# v8_4_controler.net
KiCad netlist of a schematic drawn in EAGLE
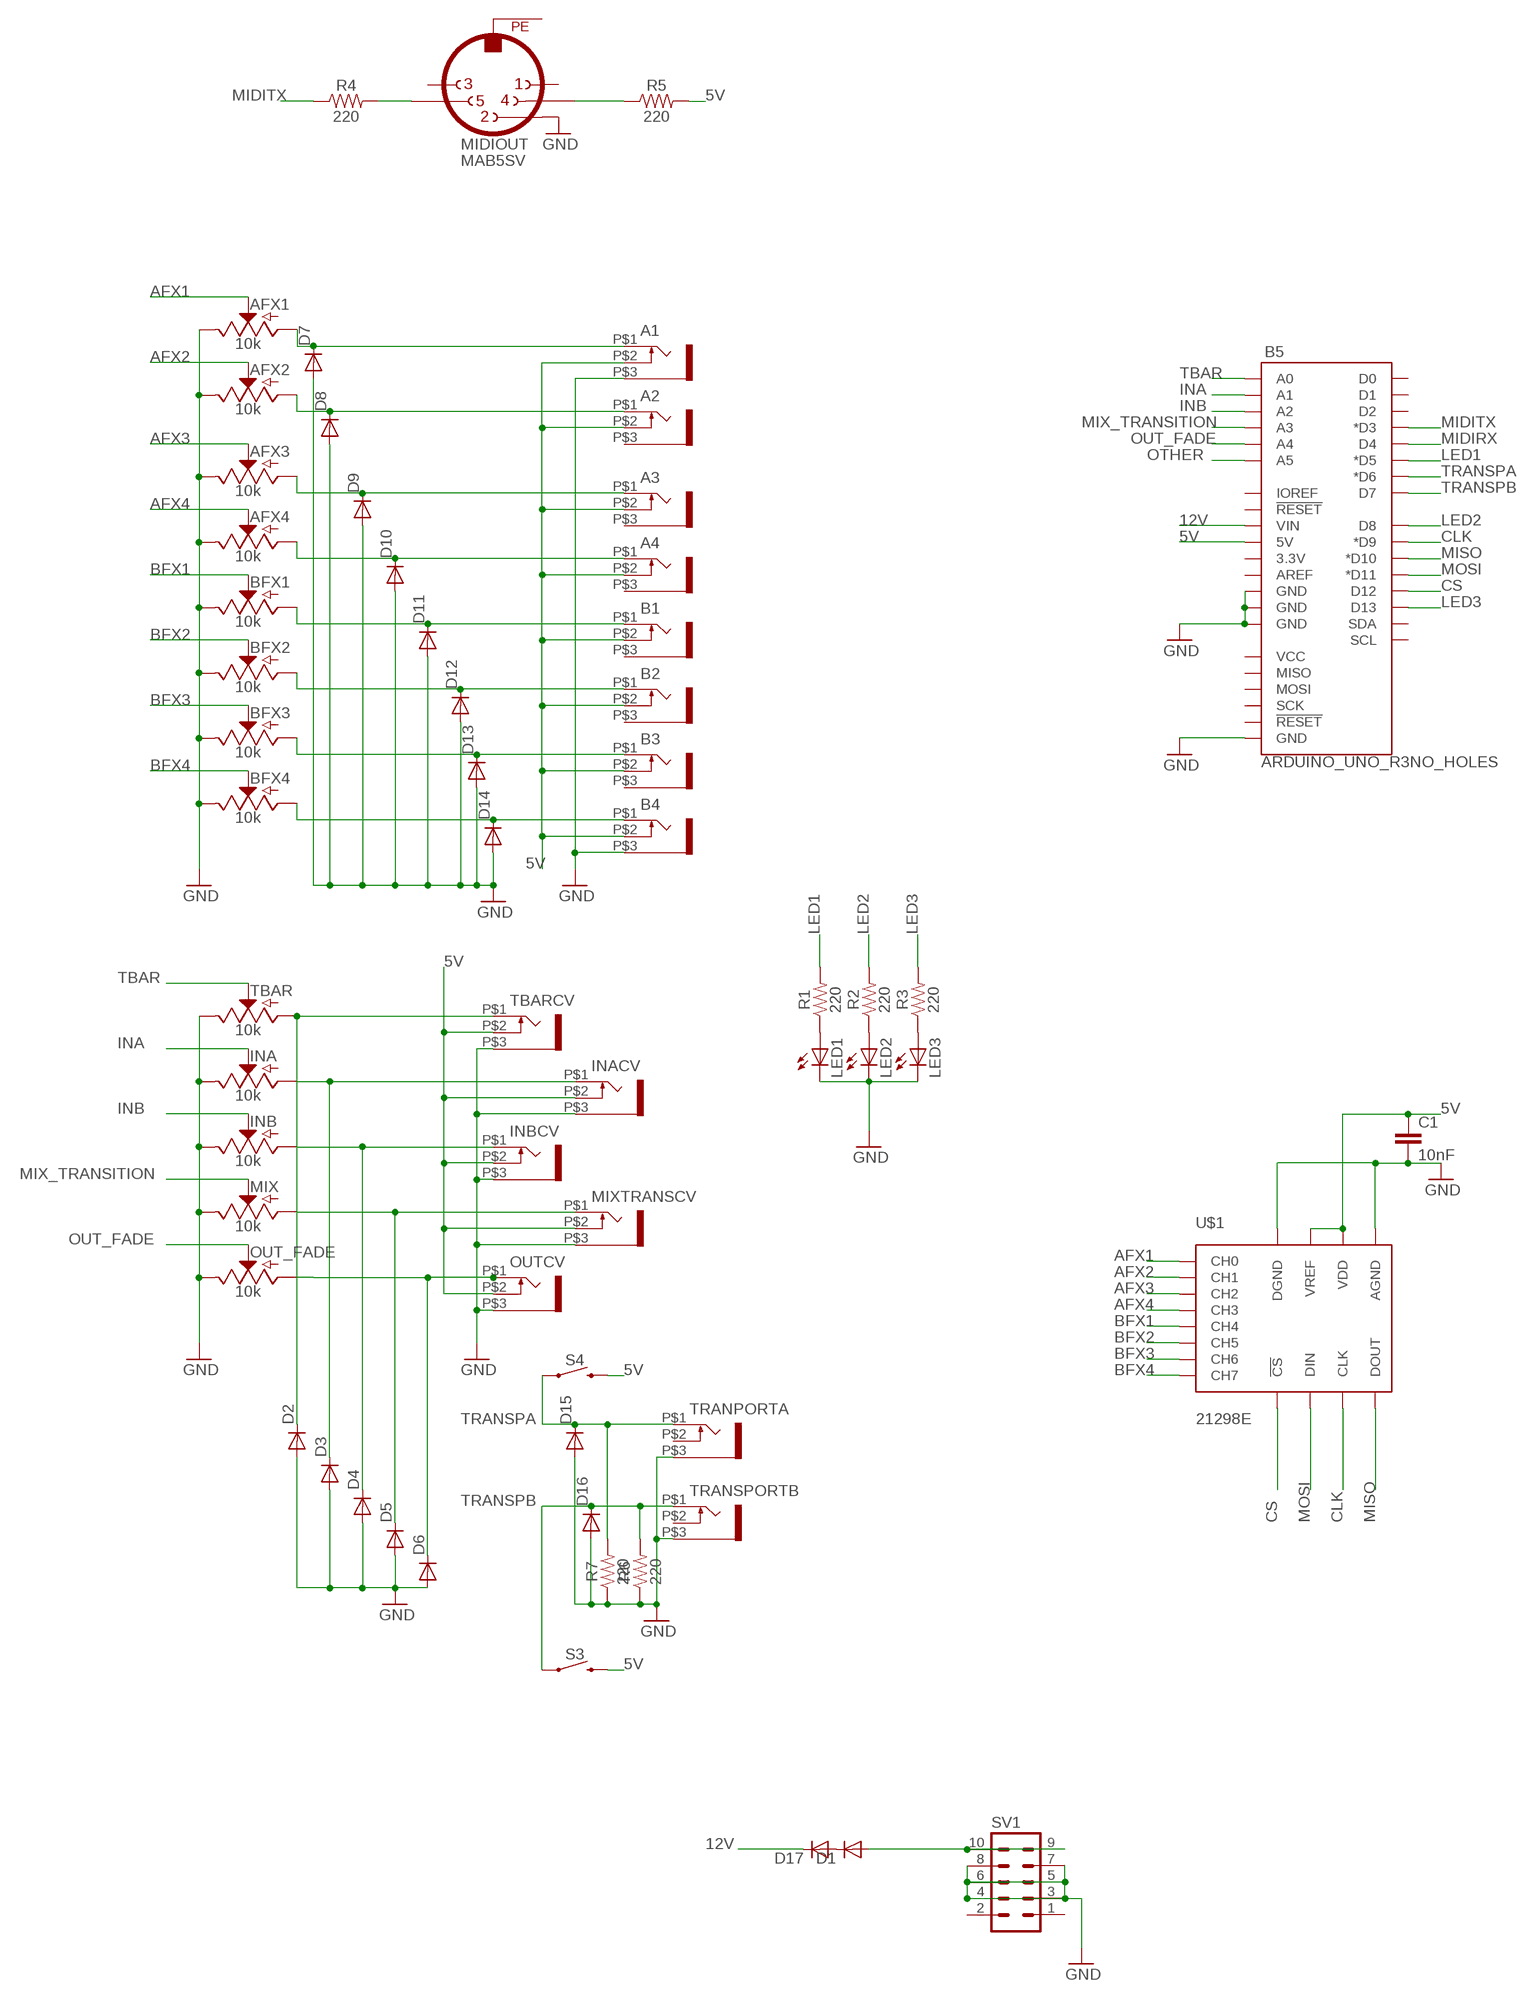
[diagram p0: schematic, sheet 1]

(export (version "E")
  (design (tool "Eeschema 10.0.6"))
  (components
    (comp (ref "A1")
      (value "WQP-PJ301M-12_JACK")
      (footprint "eagle-import:WQP-PJ301M-12_JACK")
      (fields (field (name "SPICEPREFIX") "U"))
      (libsource (lib "eagle-import") (part "WQP-PJ301M-12_JACK"))
    )
    (comp (ref "A2")
      (value "WQP-PJ301M-12_JACK")
      (footprint "eagle-import:WQP-PJ301M-12_JACK")
      (fields (field (name "SPICEPREFIX") "U"))
      (libsource (lib "eagle-import") (part "WQP-PJ301M-12_JACK"))
    )
    (comp (ref "A3")
      (value "WQP-PJ301M-12_JACK")
      (footprint "eagle-import:WQP-PJ301M-12_JACK")
      (fields (field (name "SPICEPREFIX") "U"))
      (libsource (lib "eagle-import") (part "WQP-PJ301M-12_JACK"))
    )
    (comp (ref "A4")
      (value "WQP-PJ301M-12_JACK")
      (footprint "eagle-import:WQP-PJ301M-12_JACK")
      (fields (field (name "SPICEPREFIX") "U"))
      (libsource (lib "eagle-import") (part "WQP-PJ301M-12_JACK"))
    )
    (comp (ref "AFX1")
      (value "10k")
      (footprint "eagle-import:POT-PTH-ALPS")
      (libsource (lib "eagle-import") (part "POTENTIOMETER-PTH-9MM-1/20W-20%"))
    )
    (comp (ref "AFX2")
      (value "10k")
      (footprint "eagle-import:POT-PTH-ALPS")
      (libsource (lib "eagle-import") (part "POTENTIOMETER-PTH-9MM-1/20W-20%"))
    )
    (comp (ref "AFX3")
      (value "10k")
      (footprint "eagle-import:POT-PTH-ALPS")
      (libsource (lib "eagle-import") (part "POTENTIOMETER-PTH-9MM-1/20W-20%"))
    )
    (comp (ref "AFX4")
      (value "10k")
      (footprint "eagle-import:POT-PTH-ALPS")
      (libsource (lib "eagle-import") (part "POTENTIOMETER-PTH-9MM-1/20W-20%"))
    )
    (comp (ref "B1")
      (value "WQP-PJ301M-12_JACK")
      (footprint "eagle-import:WQP-PJ301M-12_JACK")
      (fields (field (name "SPICEPREFIX") "U"))
      (libsource (lib "eagle-import") (part "WQP-PJ301M-12_JACK"))
    )
    (comp (ref "B2")
      (value "WQP-PJ301M-12_JACK")
      (footprint "eagle-import:WQP-PJ301M-12_JACK")
      (fields (field (name "SPICEPREFIX") "U"))
      (libsource (lib "eagle-import") (part "WQP-PJ301M-12_JACK"))
    )
    (comp (ref "B3")
      (value "WQP-PJ301M-12_JACK")
      (footprint "eagle-import:WQP-PJ301M-12_JACK")
      (fields (field (name "SPICEPREFIX") "U"))
      (libsource (lib "eagle-import") (part "WQP-PJ301M-12_JACK"))
    )
    (comp (ref "B4")
      (value "WQP-PJ301M-12_JACK")
      (footprint "eagle-import:WQP-PJ301M-12_JACK")
      (fields (field (name "SPICEPREFIX") "U"))
      (libsource (lib "eagle-import") (part "WQP-PJ301M-12_JACK"))
    )
    (comp (ref "B5")
      (value "ARDUINO_UNO_R3NO_HOLES")
      (footprint "eagle-import:ARDUINO_R3_NO_HOLES")
      (libsource (lib "eagle-import") (part "ARDUINO_UNO_R3NO_HOLES"))
    )
    (comp (ref "BFX1")
      (value "10k")
      (footprint "eagle-import:POT-PTH-ALPS")
      (libsource (lib "eagle-import") (part "POTENTIOMETER-PTH-9MM-1/20W-20%"))
    )
    (comp (ref "BFX2")
      (value "10k")
      (footprint "eagle-import:POT-PTH-ALPS")
      (libsource (lib "eagle-import") (part "POTENTIOMETER-PTH-9MM-1/20W-20%"))
    )
    (comp (ref "BFX3")
      (value "10k")
      (footprint "eagle-import:POT-PTH-ALPS")
      (libsource (lib "eagle-import") (part "POTENTIOMETER-PTH-9MM-1/20W-20%"))
    )
    (comp (ref "BFX4")
      (value "10k")
      (footprint "eagle-import:POT-PTH-ALPS")
      (libsource (lib "eagle-import") (part "POTENTIOMETER-PTH-9MM-1/20W-20%"))
    )
    (comp (ref "C1")
      (value "10nF")
      (footprint "eagle-import:CAP-PTH-10MM")
      (libsource (lib "eagle-import") (part "10NF-PTH-10MM-10000V-1-%"))
    )
    (comp (ref "D1")
      (value "1N4004")
      (footprint "eagle-import:DO41-10")
      (libsource (lib "eagle-import") (part "1N4004"))
    )
    (comp (ref "D2")
      (value "1N4004")
      (footprint "eagle-import:DO41-10")
      (libsource (lib "eagle-import") (part "1N4004"))
    )
    (comp (ref "D3")
      (value "1N4004")
      (footprint "eagle-import:DO41-10")
      (libsource (lib "eagle-import") (part "1N4004"))
    )
    (comp (ref "D4")
      (value "1N4004")
      (footprint "eagle-import:DO41-10")
      (libsource (lib "eagle-import") (part "1N4004"))
    )
    (comp (ref "D5")
      (value "1N4004")
      (footprint "eagle-import:DO41-10")
      (libsource (lib "eagle-import") (part "1N4004"))
    )
    (comp (ref "D6")
      (value "1N4004")
      (footprint "eagle-import:DO41-10")
      (libsource (lib "eagle-import") (part "1N4004"))
    )
    (comp (ref "D7")
      (value "1N4004")
      (footprint "eagle-import:DO41-10")
      (libsource (lib "eagle-import") (part "1N4004"))
    )
    (comp (ref "D8")
      (value "1N4004")
      (footprint "eagle-import:DO41-10")
      (libsource (lib "eagle-import") (part "1N4004"))
    )
    (comp (ref "D9")
      (value "1N4004")
      (footprint "eagle-import:DO41-10")
      (libsource (lib "eagle-import") (part "1N4004"))
    )
    (comp (ref "D10")
      (value "1N4004")
      (footprint "eagle-import:DO41-10")
      (libsource (lib "eagle-import") (part "1N4004"))
    )
    (comp (ref "D11")
      (value "1N4004")
      (footprint "eagle-import:DO41-10")
      (libsource (lib "eagle-import") (part "1N4004"))
    )
    (comp (ref "D12")
      (value "1N4004")
      (footprint "eagle-import:DO41-10")
      (libsource (lib "eagle-import") (part "1N4004"))
    )
    (comp (ref "D13")
      (value "1N4004")
      (footprint "eagle-import:DO41-10")
      (libsource (lib "eagle-import") (part "1N4004"))
    )
    (comp (ref "D14")
      (value "1N4004")
      (footprint "eagle-import:DO41-10")
      (libsource (lib "eagle-import") (part "1N4004"))
    )
    (comp (ref "D15")
      (value "1N4004")
      (footprint "eagle-import:DO41-10")
      (libsource (lib "eagle-import") (part "1N4004"))
    )
    (comp (ref "D16")
      (value "1N4004")
      (footprint "eagle-import:DO41-10")
      (libsource (lib "eagle-import") (part "1N4004"))
    )
    (comp (ref "D17")
      (value "1N4004")
      (footprint "eagle-import:DO41-10")
      (libsource (lib "eagle-import") (part "1N4004"))
    )
    (comp (ref "INA")
      (value "10k")
      (footprint "eagle-import:POT-PTH-ALPS")
      (libsource (lib "eagle-import") (part "POTENTIOMETER-PTH-9MM-1/20W-20%"))
    )
    (comp (ref "INACV")
      (value "WQP-PJ301M-12_JACK")
      (footprint "eagle-import:WQP-PJ301M-12_JACK")
      (fields (field (name "SPICEPREFIX") "U"))
      (libsource (lib "eagle-import") (part "WQP-PJ301M-12_JACK"))
    )
    (comp (ref "INB")
      (value "10k")
      (footprint "eagle-import:POT-PTH-ALPS")
      (libsource (lib "eagle-import") (part "POTENTIOMETER-PTH-9MM-1/20W-20%"))
    )
    (comp (ref "INBCV")
      (value "WQP-PJ301M-12_JACK")
      (footprint "eagle-import:WQP-PJ301M-12_JACK")
      (fields (field (name "SPICEPREFIX") "U"))
      (libsource (lib "eagle-import") (part "WQP-PJ301M-12_JACK"))
    )
    (comp (ref "LED1")
      (value "LED3MM")
      (footprint "eagle-import:LED3MM")
      (libsource (lib "eagle-import") (part "LED3MM"))
    )
    (comp (ref "LED2")
      (value "LED3MM")
      (footprint "eagle-import:LED3MM")
      (libsource (lib "eagle-import") (part "LED3MM"))
    )
    (comp (ref "LED3")
      (value "LED3MM")
      (footprint "eagle-import:LED3MM")
      (libsource (lib "eagle-import") (part "LED3MM"))
    )
    (comp (ref "MIDIOUT")
      (value "MAB5SV")
      (footprint "eagle-import:MAB5SV")
      (libsource (lib "eagle-import") (part "MAB5SV"))
    )
    (comp (ref "MIX")
      (value "10k")
      (footprint "eagle-import:POT-PTH-ALPS")
      (libsource (lib "eagle-import") (part "POTENTIOMETER-PTH-9MM-1/20W-20%"))
    )
    (comp (ref "MIXTRANSCV")
      (value "WQP-PJ301M-12_JACK")
      (footprint "eagle-import:WQP-PJ301M-12_JACK")
      (fields (field (name "SPICEPREFIX") "U"))
      (libsource (lib "eagle-import") (part "WQP-PJ301M-12_JACK"))
    )
    (comp (ref "OUTCV")
      (value "WQP-PJ301M-12_JACK")
      (footprint "eagle-import:WQP-PJ301M-12_JACK")
      (fields (field (name "SPICEPREFIX") "U"))
      (libsource (lib "eagle-import") (part "WQP-PJ301M-12_JACK"))
    )
    (comp (ref "OUT_FADE")
      (value "10k")
      (footprint "eagle-import:POT-PTH-ALPS")
      (libsource (lib "eagle-import") (part "POTENTIOMETER-PTH-9MM-1/20W-20%"))
    )
    (comp (ref "R1")
      (value "220")
      (footprint "eagle-import:AXIAL-0.3")
      (libsource (lib "eagle-import") (part "10MOHM-HORIZ-1/4W-5%"))
    )
    (comp (ref "R2")
      (value "220")
      (footprint "eagle-import:AXIAL-0.3")
      (libsource (lib "eagle-import") (part "10MOHM-HORIZ-1/4W-5%"))
    )
    (comp (ref "R3")
      (value "220")
      (footprint "eagle-import:AXIAL-0.3")
      (libsource (lib "eagle-import") (part "10MOHM-HORIZ-1/4W-5%"))
    )
    (comp (ref "R4")
      (value "220")
      (footprint "eagle-import:AXIAL-0.3")
      (libsource (lib "eagle-import") (part "10MOHM-HORIZ-1/4W-5%"))
    )
    (comp (ref "R5")
      (value "220")
      (footprint "eagle-import:AXIAL-0.3")
      (libsource (lib "eagle-import") (part "10MOHM-HORIZ-1/4W-5%"))
    )
    (comp (ref "R6")
      (value "220")
      (footprint "eagle-import:AXIAL-0.3")
      (libsource (lib "eagle-import") (part "10MOHM-HORIZ-1/4W-5%"))
    )
    (comp (ref "R7")
      (value "220")
      (footprint "eagle-import:AXIAL-0.3")
      (libsource (lib "eagle-import") (part "10MOHM-HORIZ-1/4W-5%"))
    )
    (comp (ref "S3")
      (value "MOMENTARY-SWITCH-SPST-PTH-6.0MM")
      (footprint "eagle-import:TACTILE_SWITCH_PTH_6.0MM")
      (libsource (lib "eagle-import") (part "MOMENTARY-SWITCH-SPST-PTH-6.0MM"))
    )
    (comp (ref "S4")
      (value "MOMENTARY-SWITCH-SPST-PTH-6.0MM")
      (footprint "eagle-import:TACTILE_SWITCH_PTH_6.0MM")
      (libsource (lib "eagle-import") (part "MOMENTARY-SWITCH-SPST-PTH-6.0MM"))
    )
    (comp (ref "SV1")
      (value "MA05-2")
      (footprint "eagle-import:MA05-2")
      (libsource (lib "eagle-import") (part "MA05-2"))
    )
    (comp (ref "TBAR")
      (value "10k")
      (footprint "eagle-import:POT-PTH-ALPS")
      (libsource (lib "eagle-import") (part "POTENTIOMETER-PTH-9MM-1/20W-20%"))
    )
    (comp (ref "TBARCV")
      (value "WQP-PJ301M-12_JACK")
      (footprint "eagle-import:WQP-PJ301M-12_JACK")
      (fields (field (name "SPICEPREFIX") "U"))
      (libsource (lib "eagle-import") (part "WQP-PJ301M-12_JACK"))
    )
    (comp (ref "TRANPORTA")
      (value "WQP-PJ301M-12_JACK")
      (footprint "eagle-import:WQP-PJ301M-12_JACK")
      (fields (field (name "SPICEPREFIX") "U"))
      (libsource (lib "eagle-import") (part "WQP-PJ301M-12_JACK"))
    )
    (comp (ref "TRANSPORTB")
      (value "WQP-PJ301M-12_JACK")
      (footprint "eagle-import:WQP-PJ301M-12_JACK")
      (fields (field (name "SPICEPREFIX") "U"))
      (libsource (lib "eagle-import") (part "WQP-PJ301M-12_JACK"))
    )
    (comp (ref "U$1")
      (value "21298E")
      (footprint "eagle-import:PDIP16")
      (libsource (lib "eagle-import") (part "21298E"))
    )
  )
  (nets
    (net (code "1") (name "/5V") (class "Default")
      (node (ref "A1") (pin "P$2") (pinfunction "3_P$2") (pintype "passive"))
      (node (ref "A2") (pin "P$2") (pinfunction "3_P$2") (pintype "passive"))
      (node (ref "A3") (pin "P$2") (pinfunction "3_P$2") (pintype "passive"))
      (node (ref "A4") (pin "P$2") (pinfunction "3_P$2") (pintype "passive"))
      (node (ref "B1") (pin "P$2") (pinfunction "3_P$2") (pintype "passive"))
      (node (ref "B2") (pin "P$2") (pinfunction "3_P$2") (pintype "passive"))
      (node (ref "B3") (pin "P$2") (pinfunction "3_P$2") (pintype "passive"))
      (node (ref "B4") (pin "P$2") (pinfunction "3_P$2") (pintype "passive"))
      (node (ref "B5") (pin "5V") (pinfunction "5V_5V") (pintype "bidirectional"))
      (node (ref "C1") (pin "1") (pinfunction "1_1") (pintype "passive"))
      (node (ref "INACV") (pin "P$2") (pinfunction "3_P$2") (pintype "passive"))
      (node (ref "INBCV") (pin "P$2") (pinfunction "3_P$2") (pintype "passive"))
      (node (ref "MIXTRANSCV") (pin "P$2") (pinfunction "3_P$2") (pintype "passive"))
      (node (ref "OUTCV") (pin "P$2") (pinfunction "3_P$2") (pintype "passive"))
      (node (ref "R5") (pin "P$2") (pinfunction "2_P$2") (pintype "passive"))
      (node (ref "S3") (pin "3") (pinfunction "2_3") (pintype "passive"))
      (node (ref "S4") (pin "3") (pinfunction "2_3") (pintype "passive"))
      (node (ref "TBARCV") (pin "P$2") (pinfunction "3_P$2") (pintype "passive"))
      (node (ref "U$1") (pin "P$15") (pinfunction "VREF_P$15") (pintype "bidirectional"))
      (node (ref "U$1") (pin "P$16") (pinfunction "VDD_P$16") (pintype "bidirectional"))
    )
    (net (code "2") (name "/12V") (class "Default")
      (node (ref "B5") (pin "VIN") (pinfunction "VIN_VIN") (pintype "bidirectional"))
      (node (ref "D17") (pin "C") (pinfunction "C_C") (pintype "passive"))
    )
    (net (code "3") (name "/AFX1") (class "Default")
      (node (ref "AFX1") (pin "P$2") (pinfunction "S_P$2") (pintype "passive"))
      (node (ref "U$1") (pin "P$1") (pinfunction "CH0_P$1") (pintype "bidirectional"))
    )
    (net (code "4") (name "/AFX2") (class "Default")
      (node (ref "AFX2") (pin "P$2") (pinfunction "S_P$2") (pintype "passive"))
      (node (ref "U$1") (pin "P$2") (pinfunction "CH1_P$2") (pintype "bidirectional"))
    )
    (net (code "5") (name "/AFX3") (class "Default")
      (node (ref "AFX3") (pin "P$2") (pinfunction "S_P$2") (pintype "passive"))
      (node (ref "U$1") (pin "P$3") (pinfunction "CH2_P$3") (pintype "bidirectional"))
    )
    (net (code "6") (name "/AFX4") (class "Default")
      (node (ref "AFX4") (pin "P$2") (pinfunction "S_P$2") (pintype "passive"))
      (node (ref "U$1") (pin "P$4") (pinfunction "CH3_P$4") (pintype "bidirectional"))
    )
    (net (code "7") (name "/BFX1") (class "Default")
      (node (ref "BFX1") (pin "P$2") (pinfunction "S_P$2") (pintype "passive"))
      (node (ref "U$1") (pin "P$5") (pinfunction "CH4_P$5") (pintype "bidirectional"))
    )
    (net (code "8") (name "/BFX2") (class "Default")
      (node (ref "BFX2") (pin "P$2") (pinfunction "S_P$2") (pintype "passive"))
      (node (ref "U$1") (pin "P$6") (pinfunction "CH5_P$6") (pintype "bidirectional"))
    )
    (net (code "9") (name "/BFX3") (class "Default")
      (node (ref "BFX3") (pin "P$2") (pinfunction "S_P$2") (pintype "passive"))
      (node (ref "U$1") (pin "P$7") (pinfunction "CH6_P$7") (pintype "bidirectional"))
    )
    (net (code "10") (name "/BFX4") (class "Default")
      (node (ref "BFX4") (pin "P$2") (pinfunction "S_P$2") (pintype "passive"))
      (node (ref "U$1") (pin "P$8") (pinfunction "CH7_P$8") (pintype "bidirectional"))
    )
    (net (code "11") (name "/CLK") (class "Default")
      (node (ref "B5") (pin "D9") (pinfunction "*D9_D9") (pintype "bidirectional"))
      (node (ref "U$1") (pin "P$13") (pinfunction "CLK_P$13") (pintype "bidirectional"))
    )
    (net (code "12") (name "/CS") (class "Default")
      (node (ref "B5") (pin "D12") (pinfunction "D12_D12") (pintype "bidirectional"))
      (node (ref "U$1") (pin "P$10") (pinfunction "~{CS}_P$10") (pintype "bidirectional"))
    )
    (net (code "13") (name "/INA") (class "Default")
      (node (ref "B5") (pin "A1") (pinfunction "A1_A1") (pintype "bidirectional"))
      (node (ref "INA") (pin "P$2") (pinfunction "S_P$2") (pintype "passive"))
    )
    (net (code "14") (name "/INB") (class "Default")
      (node (ref "B5") (pin "A2") (pinfunction "A2_A2") (pintype "bidirectional"))
      (node (ref "INB") (pin "P$2") (pinfunction "S_P$2") (pintype "passive"))
    )
    (net (code "15") (name "/LED1") (class "Default")
      (node (ref "B5") (pin "D5") (pinfunction "*D5_D5") (pintype "bidirectional"))
      (node (ref "R1") (pin "P$2") (pinfunction "2_P$2") (pintype "passive"))
    )
    (net (code "16") (name "/LED2") (class "Default")
      (node (ref "B5") (pin "D8") (pinfunction "D8_D8") (pintype "bidirectional"))
      (node (ref "R2") (pin "P$2") (pinfunction "2_P$2") (pintype "passive"))
    )
    (net (code "17") (name "/LED3") (class "Default")
      (node (ref "B5") (pin "D13") (pinfunction "D13_D13") (pintype "bidirectional"))
      (node (ref "R3") (pin "P$2") (pinfunction "2_P$2") (pintype "passive"))
    )
    (net (code "18") (name "/MIDIRX") (class "Default")
      (node (ref "B5") (pin "D4") (pinfunction "D4_D4") (pintype "bidirectional"))
    )
    (net (code "19") (name "/MIDITX") (class "Default")
      (node (ref "B5") (pin "D3") (pinfunction "*D3_D3") (pintype "bidirectional"))
      (node (ref "R4") (pin "P$1") (pinfunction "1_P$1") (pintype "passive"))
    )
    (net (code "20") (name "/MISO") (class "Default")
      (node (ref "B5") (pin "D10") (pinfunction "*D10_D10") (pintype "bidirectional"))
      (node (ref "U$1") (pin "P$12") (pinfunction "DOUT_P$12") (pintype "bidirectional"))
    )
    (net (code "21") (name "/MIX_TRANSITION") (class "Default")
      (node (ref "B5") (pin "A3") (pinfunction "A3_A3") (pintype "bidirectional"))
      (node (ref "MIX") (pin "P$2") (pinfunction "S_P$2") (pintype "passive"))
    )
    (net (code "22") (name "/MOSI") (class "Default")
      (node (ref "B5") (pin "D11") (pinfunction "*D11_D11") (pintype "bidirectional"))
      (node (ref "U$1") (pin "P$11") (pinfunction "DIN_P$11") (pintype "bidirectional"))
    )
    (net (code "23") (name "/OTHER") (class "Default")
      (node (ref "B5") (pin "A5") (pinfunction "A5_A5") (pintype "bidirectional"))
    )
    (net (code "24") (name "/OUT_FADE") (class "Default")
      (node (ref "B5") (pin "A4") (pinfunction "A4_A4") (pintype "bidirectional"))
      (node (ref "OUT_FADE") (pin "P$2") (pinfunction "S_P$2") (pintype "passive"))
    )
    (net (code "25") (name "/PE") (class "Default")
      (node (ref "MIDIOUT") (pin "PE") (pinfunction "PE_PE") (pintype "power_in"))
    )
    (net (code "26") (name "/TBAR") (class "Default")
      (node (ref "B5") (pin "A0") (pinfunction "A0_A0") (pintype "bidirectional"))
      (node (ref "TBAR") (pin "P$2") (pinfunction "S_P$2") (pintype "passive"))
    )
    (net (code "27") (name "/TRANSPA") (class "Default")
      (node (ref "B5") (pin "D6") (pinfunction "*D6_D6") (pintype "bidirectional"))
      (node (ref "D15") (pin "C") (pinfunction "C_C") (pintype "passive"))
      (node (ref "R7") (pin "P$2") (pinfunction "2_P$2") (pintype "passive"))
      (node (ref "S4") (pin "1") (pinfunction "1_1") (pintype "passive"))
      (node (ref "TRANPORTA") (pin "P$1") (pinfunction "2_P$1") (pintype "passive"))
    )
    (net (code "28") (name "/TRANSPB") (class "Default")
      (node (ref "B5") (pin "D7") (pinfunction "D7_D7") (pintype "bidirectional"))
      (node (ref "D16") (pin "C") (pinfunction "C_C") (pintype "passive"))
      (node (ref "R6") (pin "P$2") (pinfunction "2_P$2") (pintype "passive"))
      (node (ref "S3") (pin "1") (pinfunction "1_1") (pintype "passive"))
      (node (ref "TRANSPORTB") (pin "P$1") (pinfunction "2_P$1") (pintype "passive"))
    )
    (net (code "29") (name "GND") (class "Default")
      (node (ref "A1") (pin "P$3") (pinfunction "1_P$3") (pintype "passive"))
      (node (ref "AFX1") (pin "P$1") (pinfunction "E_P$1") (pintype "passive"))
      (node (ref "AFX2") (pin "P$1") (pinfunction "E_P$1") (pintype "passive"))
      (node (ref "AFX3") (pin "P$1") (pinfunction "E_P$1") (pintype "passive"))
      (node (ref "AFX4") (pin "P$1") (pinfunction "E_P$1") (pintype "passive"))
      (node (ref "B4") (pin "P$3") (pinfunction "1_P$3") (pintype "passive"))
      (node (ref "B5") (pin "GND@1") (pinfunction "GND_GND@1") (pintype "bidirectional"))
      (node (ref "B5") (pin "GND@2") (pinfunction "GND_GND@2") (pintype "bidirectional"))
      (node (ref "B5") (pin "GND@3") (pinfunction "GND_GND@3") (pintype "bidirectional"))
      (node (ref "B5") (pin "GND@4") (pinfunction "GND_GND@4") (pintype "bidirectional"))
      (node (ref "BFX1") (pin "P$1") (pinfunction "E_P$1") (pintype "passive"))
      (node (ref "BFX2") (pin "P$1") (pinfunction "E_P$1") (pintype "passive"))
      (node (ref "BFX3") (pin "P$1") (pinfunction "E_P$1") (pintype "passive"))
      (node (ref "BFX4") (pin "P$1") (pinfunction "E_P$1") (pintype "passive"))
      (node (ref "C1") (pin "2") (pinfunction "2_2") (pintype "passive"))
      (node (ref "D10") (pin "A") (pinfunction "A_A") (pintype "passive"))
      (node (ref "D11") (pin "A") (pinfunction "A_A") (pintype "passive"))
      (node (ref "D12") (pin "A") (pinfunction "A_A") (pintype "passive"))
      (node (ref "D13") (pin "A") (pinfunction "A_A") (pintype "passive"))
      (node (ref "D14") (pin "A") (pinfunction "A_A") (pintype "passive"))
      (node (ref "D15") (pin "A") (pinfunction "A_A") (pintype "passive"))
      (node (ref "D16") (pin "A") (pinfunction "A_A") (pintype "passive"))
      (node (ref "D2") (pin "A") (pinfunction "A_A") (pintype "passive"))
      (node (ref "D3") (pin "A") (pinfunction "A_A") (pintype "passive"))
      (node (ref "D4") (pin "A") (pinfunction "A_A") (pintype "passive"))
      (node (ref "D5") (pin "A") (pinfunction "A_A") (pintype "passive"))
      (node (ref "D6") (pin "A") (pinfunction "A_A") (pintype "passive"))
      (node (ref "D7") (pin "A") (pinfunction "A_A") (pintype "passive"))
      (node (ref "D8") (pin "A") (pinfunction "A_A") (pintype "passive"))
      (node (ref "D9") (pin "A") (pinfunction "A_A") (pintype "passive"))
      (node (ref "INA") (pin "P$1") (pinfunction "E_P$1") (pintype "passive"))
      (node (ref "INACV") (pin "P$3") (pinfunction "1_P$3") (pintype "passive"))
      (node (ref "INB") (pin "P$1") (pinfunction "E_P$1") (pintype "passive"))
      (node (ref "INBCV") (pin "P$3") (pinfunction "1_P$3") (pintype "passive"))
      (node (ref "LED1") (pin "K") (pinfunction "C_K") (pintype "passive"))
      (node (ref "LED2") (pin "K") (pinfunction "C_K") (pintype "passive"))
      (node (ref "LED3") (pin "K") (pinfunction "C_K") (pintype "passive"))
      (node (ref "MIDIOUT") (pin "2") (pinfunction "2_2") (pintype "passive"))
      (node (ref "MIX") (pin "P$1") (pinfunction "E_P$1") (pintype "passive"))
      (node (ref "MIXTRANSCV") (pin "P$3") (pinfunction "1_P$3") (pintype "passive"))
      (node (ref "OUTCV") (pin "P$3") (pinfunction "1_P$3") (pintype "passive"))
      (node (ref "OUT_FADE") (pin "P$1") (pinfunction "E_P$1") (pintype "passive"))
      (node (ref "R6") (pin "P$1") (pinfunction "1_P$1") (pintype "passive"))
      (node (ref "R7") (pin "P$1") (pinfunction "1_P$1") (pintype "passive"))
      (node (ref "SV1") (pin "3") (pinfunction "3_3") (pintype "passive"))
      (node (ref "SV1") (pin "4") (pinfunction "4_4") (pintype "passive"))
      (node (ref "SV1") (pin "5") (pinfunction "5_5") (pintype "passive"))
      (node (ref "SV1") (pin "6") (pinfunction "6_6") (pintype "passive"))
      (node (ref "SV1") (pin "7") (pinfunction "7_7") (pintype "passive"))
      (node (ref "SV1") (pin "8") (pinfunction "8_8") (pintype "passive"))
      (node (ref "TBAR") (pin "P$1") (pinfunction "E_P$1") (pintype "passive"))
      (node (ref "TBARCV") (pin "P$3") (pinfunction "1_P$3") (pintype "passive"))
      (node (ref "TRANPORTA") (pin "P$3") (pinfunction "1_P$3") (pintype "passive"))
      (node (ref "TRANSPORTB") (pin "P$3") (pinfunction "1_P$3") (pintype "passive"))
      (node (ref "U$1") (pin "P$14") (pinfunction "AGND_P$14") (pintype "bidirectional"))
      (node (ref "U$1") (pin "P$9") (pinfunction "DGND_P$9") (pintype "bidirectional"))
    )
    (net (code "30") (name "Net-(A1-2)") (class "Default")
      (node (ref "A1") (pin "P$1") (pinfunction "2_P$1") (pintype "passive"))
      (node (ref "AFX1") (pin "P$3") (pinfunction "A_P$3") (pintype "passive"))
      (node (ref "D7") (pin "C") (pinfunction "C_C") (pintype "passive"))
    )
    (net (code "31") (name "Net-(A2-2)") (class "Default")
      (node (ref "A2") (pin "P$1") (pinfunction "2_P$1") (pintype "passive"))
      (node (ref "AFX2") (pin "P$3") (pinfunction "A_P$3") (pintype "passive"))
      (node (ref "D8") (pin "C") (pinfunction "C_C") (pintype "passive"))
    )
    (net (code "32") (name "Net-(A3-2)") (class "Default")
      (node (ref "A3") (pin "P$1") (pinfunction "2_P$1") (pintype "passive"))
      (node (ref "AFX3") (pin "P$3") (pinfunction "A_P$3") (pintype "passive"))
      (node (ref "D9") (pin "C") (pinfunction "C_C") (pintype "passive"))
    )
    (net (code "33") (name "Net-(A4-2)") (class "Default")
      (node (ref "A4") (pin "P$1") (pinfunction "2_P$1") (pintype "passive"))
      (node (ref "AFX4") (pin "P$3") (pinfunction "A_P$3") (pintype "passive"))
      (node (ref "D10") (pin "C") (pinfunction "C_C") (pintype "passive"))
    )
    (net (code "34") (name "Net-(B1-2)") (class "Default")
      (node (ref "B1") (pin "P$1") (pinfunction "2_P$1") (pintype "passive"))
      (node (ref "BFX1") (pin "P$3") (pinfunction "A_P$3") (pintype "passive"))
      (node (ref "D11") (pin "C") (pinfunction "C_C") (pintype "passive"))
    )
    (net (code "35") (name "Net-(B2-2)") (class "Default")
      (node (ref "B2") (pin "P$1") (pinfunction "2_P$1") (pintype "passive"))
      (node (ref "BFX2") (pin "P$3") (pinfunction "A_P$3") (pintype "passive"))
      (node (ref "D12") (pin "C") (pinfunction "C_C") (pintype "passive"))
    )
    (net (code "36") (name "Net-(B3-2)") (class "Default")
      (node (ref "B3") (pin "P$1") (pinfunction "2_P$1") (pintype "passive"))
      (node (ref "BFX3") (pin "P$3") (pinfunction "A_P$3") (pintype "passive"))
      (node (ref "D13") (pin "C") (pinfunction "C_C") (pintype "passive"))
    )
    (net (code "37") (name "Net-(B4-2)") (class "Default")
      (node (ref "B4") (pin "P$1") (pinfunction "2_P$1") (pintype "passive"))
      (node (ref "BFX4") (pin "P$3") (pinfunction "A_P$3") (pintype "passive"))
      (node (ref "D14") (pin "C") (pinfunction "C_C") (pintype "passive"))
    )
    (net (code "38") (name "Net-(D1-PadA)") (class "Default")
      (node (ref "D1") (pin "A") (pinfunction "A_A") (pintype "passive"))
      (node (ref "SV1") (pin "10") (pinfunction "10_10") (pintype "passive"))
      (node (ref "SV1") (pin "9") (pinfunction "9_9") (pintype "passive"))
    )
    (net (code "39") (name "Net-(D1-PadC)") (class "Default")
      (node (ref "D1") (pin "C") (pinfunction "C_C") (pintype "passive"))
      (node (ref "D17") (pin "A") (pinfunction "A_A") (pintype "passive"))
    )
    (net (code "40") (name "Net-(INA-A)") (class "Default")
      (node (ref "D3") (pin "C") (pinfunction "C_C") (pintype "passive"))
      (node (ref "INA") (pin "P$3") (pinfunction "A_P$3") (pintype "passive"))
      (node (ref "INACV") (pin "P$1") (pinfunction "2_P$1") (pintype "passive"))
    )
    (net (code "41") (name "Net-(INB-A)") (class "Default")
      (node (ref "D4") (pin "C") (pinfunction "C_C") (pintype "passive"))
      (node (ref "INB") (pin "P$3") (pinfunction "A_P$3") (pintype "passive"))
      (node (ref "INBCV") (pin "P$1") (pinfunction "2_P$1") (pintype "passive"))
    )
    (net (code "42") (name "Net-(MIX-A)") (class "Default")
      (node (ref "D5") (pin "C") (pinfunction "C_C") (pintype "passive"))
      (node (ref "MIX") (pin "P$3") (pinfunction "A_P$3") (pintype "passive"))
      (node (ref "MIXTRANSCV") (pin "P$1") (pinfunction "2_P$1") (pintype "passive"))
    )
    (net (code "43") (name "Net-(OUTCV-2)") (class "Default")
      (node (ref "D6") (pin "C") (pinfunction "C_C") (pintype "passive"))
      (node (ref "OUTCV") (pin "P$1") (pinfunction "2_P$1") (pintype "passive"))
      (node (ref "OUT_FADE") (pin "P$3") (pinfunction "A_P$3") (pintype "passive"))
    )
    (net (code "44") (name "Net-(R1-1)") (class "Default")
      (node (ref "LED1") (pin "A") (pinfunction "A_A") (pintype "passive"))
      (node (ref "R1") (pin "P$1") (pinfunction "1_P$1") (pintype "passive"))
    )
    (net (code "45") (name "Net-(R2-1)") (class "Default")
      (node (ref "LED2") (pin "A") (pinfunction "A_A") (pintype "passive"))
      (node (ref "R2") (pin "P$1") (pinfunction "1_P$1") (pintype "passive"))
    )
    (net (code "46") (name "Net-(R3-1)") (class "Default")
      (node (ref "LED3") (pin "A") (pinfunction "A_A") (pintype "passive"))
      (node (ref "R3") (pin "P$1") (pinfunction "1_P$1") (pintype "passive"))
    )
    (net (code "47") (name "Net-(R4-2)") (class "Default")
      (node (ref "MIDIOUT") (pin "5") (pinfunction "5_5") (pintype "passive"))
      (node (ref "R4") (pin "P$2") (pinfunction "2_P$2") (pintype "passive"))
    )
    (net (code "48") (name "Net-(R5-1)") (class "Default")
      (node (ref "MIDIOUT") (pin "4") (pinfunction "4_4") (pintype "passive"))
      (node (ref "R5") (pin "P$1") (pinfunction "1_P$1") (pintype "passive"))
    )
    (net (code "49") (name "Net-(TBAR-A)") (class "Default")
      (node (ref "D2") (pin "C") (pinfunction "C_C") (pintype "passive"))
      (node (ref "TBAR") (pin "P$3") (pinfunction "A_P$3") (pintype "passive"))
      (node (ref "TBARCV") (pin "P$1") (pinfunction "2_P$1") (pintype "passive"))
    )
    (net (code "50") (name "unconnected-(A2-1-PadP$3)") (class "Default")
      (node (ref "A2") (pin "P$3") (pinfunction "1_P$3") (pintype "passive"))
    )
    (net (code "51") (name "unconnected-(A3-1-PadP$3)") (class "Default")
      (node (ref "A3") (pin "P$3") (pinfunction "1_P$3") (pintype "passive"))
    )
    (net (code "52") (name "unconnected-(A4-1-PadP$3)") (class "Default")
      (node (ref "A4") (pin "P$3") (pinfunction "1_P$3") (pintype "passive"))
    )
    (net (code "53") (name "unconnected-(B1-1-PadP$3)") (class "Default")
      (node (ref "B1") (pin "P$3") (pinfunction "1_P$3") (pintype "passive"))
    )
    (net (code "54") (name "unconnected-(B2-1-PadP$3)") (class "Default")
      (node (ref "B2") (pin "P$3") (pinfunction "1_P$3") (pintype "passive"))
    )
    (net (code "55") (name "unconnected-(B3-1-PadP$3)") (class "Default")
      (node (ref "B3") (pin "P$3") (pinfunction "1_P$3") (pintype "passive"))
    )
    (net (code "56") (name "unconnected-(B5-Pad3.3V)") (class "Default")
      (node (ref "B5") (pin "3.3V") (pinfunction "3.3V_3.3V") (pintype "bidirectional"))
    )
    (net (code "57") (name "unconnected-(B5-PadAREF)") (class "Default")
      (node (ref "B5") (pin "AREF") (pinfunction "AREF_AREF") (pintype "bidirectional"))
    )
    (net (code "58") (name "unconnected-(B5-PadD0)") (class "Default")
      (node (ref "B5") (pin "D0") (pinfunction "D0_D0") (pintype "bidirectional"))
    )
    (net (code "59") (name "unconnected-(B5-PadD1)") (class "Default")
      (node (ref "B5") (pin "D1") (pinfunction "D1_D1") (pintype "bidirectional"))
    )
    (net (code "60") (name "unconnected-(B5-PadD2)") (class "Default")
      (node (ref "B5") (pin "D2") (pinfunction "D2_D2") (pintype "bidirectional"))
    )
    (net (code "61") (name "unconnected-(B5-PadIOREF)") (class "Default")
      (node (ref "B5") (pin "IOREF") (pinfunction "IOREF_IOREF") (pintype "bidirectional"))
    )
    (net (code "62") (name "unconnected-(B5-PadMISO)") (class "Default")
      (node (ref "B5") (pin "MISO") (pinfunction "MISO_MISO") (pintype "bidirectional"))
    )
    (net (code "63") (name "unconnected-(B5-PadMOSI)") (class "Default")
      (node (ref "B5") (pin "MOSI") (pinfunction "MOSI_MOSI") (pintype "bidirectional"))
    )
    (net (code "64") (name "unconnected-(B5-PadSCK)") (class "Default")
      (node (ref "B5") (pin "SCK") (pinfunction "SCK_SCK") (pintype "bidirectional"))
    )
    (net (code "65") (name "unconnected-(B5-PadSCL)") (class "Default")
      (node (ref "B5") (pin "SCL") (pinfunction "SCL_SCL") (pintype "bidirectional"))
    )
    (net (code "66") (name "unconnected-(B5-PadSDA)") (class "Default")
      (node (ref "B5") (pin "SDA") (pinfunction "SDA_SDA") (pintype "bidirectional"))
    )
    (net (code "67") (name "unconnected-(B5-PadVCC)") (class "Default")
      (node (ref "B5") (pin "VCC") (pinfunction "VCC_VCC") (pintype "bidirectional"))
    )
    (net (code "68") (name "unconnected-(B5-~{RESET}-PadRESET@1)") (class "Default")
      (node (ref "B5") (pin "RESET@1") (pinfunction "~{RESET}_RESET@1") (pintype "bidirectional"))
    )
    (net (code "69") (name "unconnected-(B5-~{RESET}-PadRESET@2)") (class "Default")
      (node (ref "B5") (pin "RESET@2") (pinfunction "~{RESET}_RESET@2") (pintype "bidirectional"))
    )
    (net (code "70") (name "unconnected-(MIDIOUT-Pad1)") (class "Default")
      (node (ref "MIDIOUT") (pin "1") (pinfunction "1_1") (pintype "passive"))
    )
    (net (code "71") (name "unconnected-(MIDIOUT-Pad3)") (class "Default")
      (node (ref "MIDIOUT") (pin "3") (pinfunction "3_3") (pintype "passive"))
    )
    (net (code "72") (name "unconnected-(SV1-Pad1)") (class "Default")
      (node (ref "SV1") (pin "1") (pinfunction "1_1") (pintype "passive"))
    )
    (net (code "73") (name "unconnected-(SV1-Pad2)") (class "Default")
      (node (ref "SV1") (pin "2") (pinfunction "2_2") (pintype "passive"))
    )
    (net (code "74") (name "unconnected-(TRANPORTA-3-PadP$2)") (class "Default")
      (node (ref "TRANPORTA") (pin "P$2") (pinfunction "3_P$2") (pintype "passive"))
    )
    (net (code "75") (name "unconnected-(TRANSPORTB-3-PadP$2)") (class "Default")
      (node (ref "TRANSPORTB") (pin "P$2") (pinfunction "3_P$2") (pintype "passive"))
    )
  )
)
